# schematic.net
KiCad netlist of a schematic drawn in Altium Designer
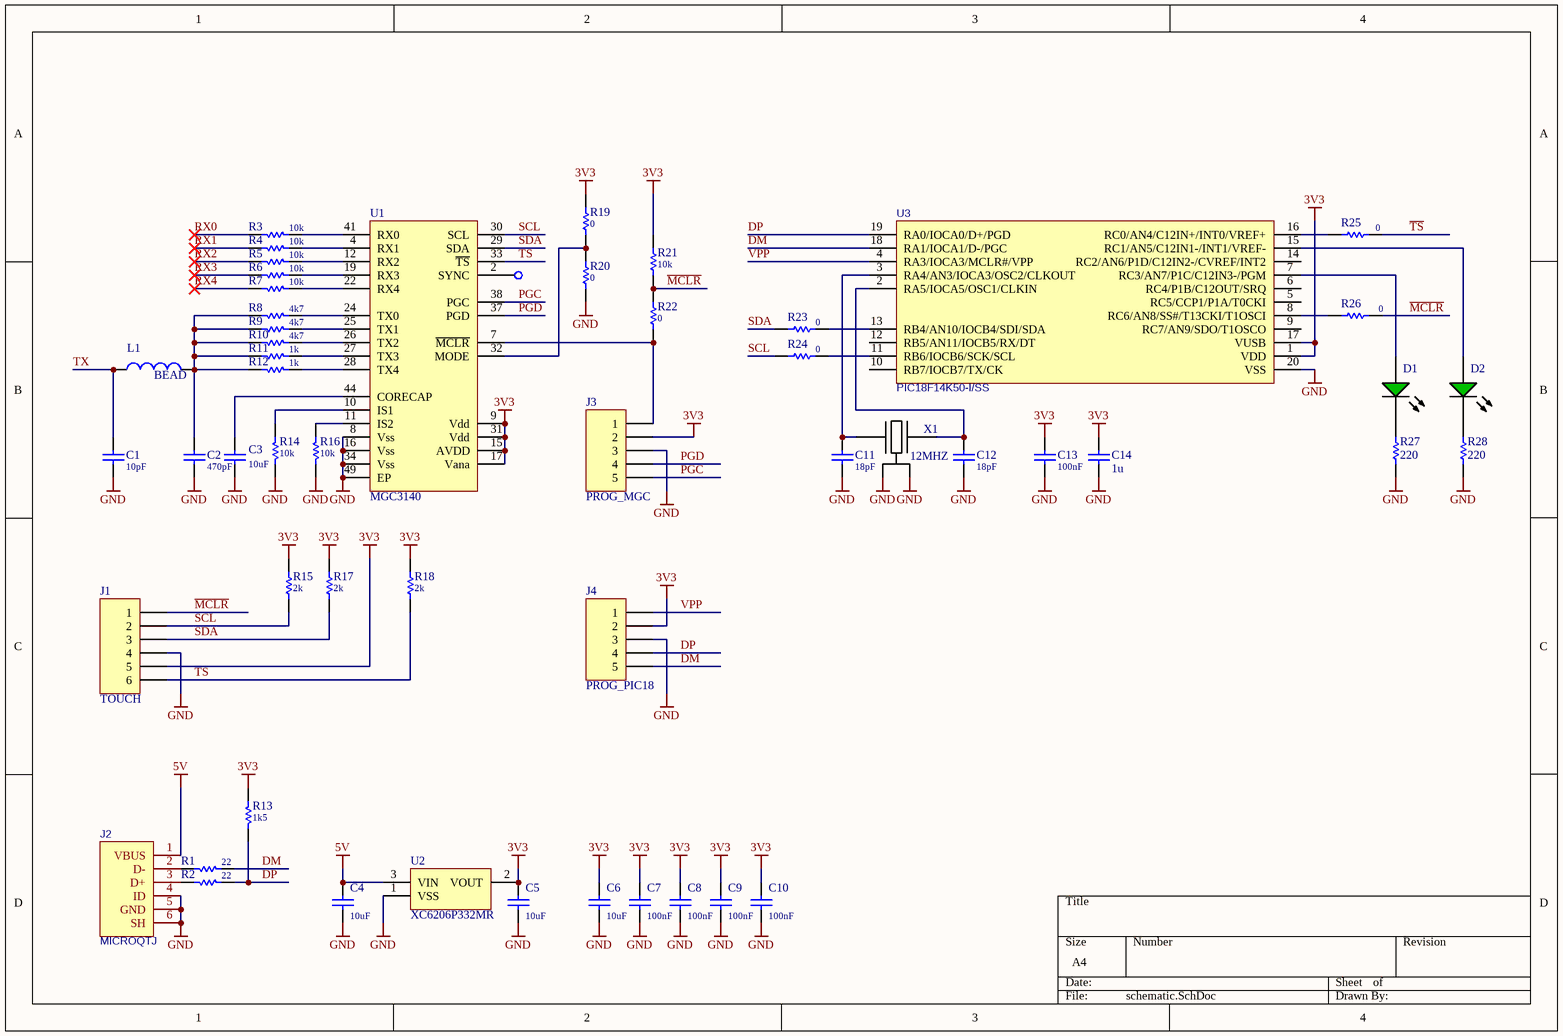
[diagram p0: schematic.SchDoc]

(export (version "E")
  (design (tool "Eeschema 10.0.6"))
  (components
    (comp (ref "C1")
      (value "10pF")
      (footprint "C0603")
      (libsource (lib "Miscellaneous Devices") (part "CAP"))
    )
    (comp (ref "C2")
      (value "470pF")
      (footprint "C0603")
      (libsource (lib "Miscellaneous Devices") (part "CAP"))
    )
    (comp (ref "C3")
      (value "10uF")
      (footprint "C0805")
      (libsource (lib "Miscellaneous Devices") (part "CAP"))
    )
    (comp (ref "C4")
      (value "10uF")
      (footprint "C1206")
      (libsource (lib "Miscellaneous Devices") (part "CAP"))
    )
    (comp (ref "C5")
      (value "10uF")
      (footprint "C1206")
      (libsource (lib "Miscellaneous Devices") (part "CAP"))
    )
    (comp (ref "C6")
      (value "10uF")
      (footprint "C0805")
      (libsource (lib "Miscellaneous Devices") (part "CAP"))
    )
    (comp (ref "C7")
      (value "100nF")
      (footprint "C0402")
      (libsource (lib "Miscellaneous Devices") (part "CAP"))
    )
    (comp (ref "C8")
      (value "100nF")
      (footprint "C0402")
      (libsource (lib "Miscellaneous Devices") (part "CAP"))
    )
    (comp (ref "C9")
      (value "100nF")
      (footprint "C0402")
      (libsource (lib "Miscellaneous Devices") (part "CAP"))
    )
    (comp (ref "C10")
      (value "100nF")
      (footprint "C0402")
      (libsource (lib "Miscellaneous Devices") (part "CAP"))
    )
    (comp (ref "C11")
      (value "18pF")
      (footprint "C0402")
      (description "18pF 50V 0402")
      (fields (field (name "LCSC PART NUMBER") "C33149"))
      (libsource (lib "Miscellaneous Devices") (part "CAP"))
    )
    (comp (ref "C12")
      (value "18pF")
      (footprint "C0402")
      (description "18pF 50V 0402")
      (fields (field (name "LCSC PART NUMBER") "C33149"))
      (libsource (lib "Miscellaneous Devices") (part "CAP"))
    )
    (comp (ref "C13")
      (value "100nF")
      (footprint "C0402")
      (libsource (lib "Miscellaneous Devices") (part "CAP"))
    )
    (comp (ref "C14") (value "1u") (footprint "C0603") (libsource (lib "Miscellaneous Devices") (part "Cap")))
    (comp (ref "D1")
      (value "GRN")
      (footprint "LED-0603-GRN")
      (description "LED 0603 GRN")
      (libsource (lib "Miscellaneous Devices") (part "LED-0603-GREEN"))
    )
    (comp (ref "D2")
      (value "GRN")
      (footprint "LED-0603-GRN")
      (description "LED 0603 GRN")
      (libsource (lib "Miscellaneous Devices") (part "LED-0603-GREEN"))
    )
    (comp (ref "DN1")
      (value "~")
      (footprint "PAD_CAST2_0.8MM")
      (libsource (lib "Schlib1") (part "dummy net"))
    )
    (comp (ref "J1") (value "TOUCH") (footprint "HDR-1X6_2.54") (libsource (lib "Schlib1") (part "Header 3")))
    (comp (ref "J2")
      (value "MICROQTJ")
      (footprint "CONN-USB-MICRO_#1")
      (libsource (lib "Schlib2") (part "MICROQTJ"))
    )
    (comp (ref "J3")
      (value "PROG_MGC")
      (footprint "HDR-1X5_2.54")
      (libsource (lib "Schlib1") (part "Header 5"))
    )
    (comp (ref "J4")
      (value "PROG_PIC18")
      (footprint "HDR-1X5_2.54")
      (libsource (lib "Schlib1") (part "Header 5"))
    )
    (comp (ref "L1")
      (value "BEAD")
      (footprint "L0603")
      (description "380mΩ ±25% 600Ω@100MHz 0603 Ferrite Beads")
      (fields (field (name "LCSC PART NUMBER") "C19330"))
      (libsource (lib "Miscellaneous Devices") (part "BLM18AG601SN1D"))
    )
    (comp (ref "R1") (value "22") (footprint "R0603") (libsource (lib "Miscellaneous Devices") (part "RES")))
    (comp (ref "R2") (value "22") (footprint "R0603") (libsource (lib "Miscellaneous Devices") (part "RES")))
    (comp (ref "R3")
      (value "10k")
      (footprint "R0603")
      (description "10k 0603")
      (libsource (lib "Miscellaneous Devices") (part "RES"))
    )
    (comp (ref "R4")
      (value "10k")
      (footprint "R0603")
      (description "10k 0603")
      (libsource (lib "Miscellaneous Devices") (part "RES"))
    )
    (comp (ref "R5")
      (value "10k")
      (footprint "R0603")
      (description "10k 0603")
      (libsource (lib "Miscellaneous Devices") (part "RES"))
    )
    (comp (ref "R6")
      (value "10k")
      (footprint "R0603")
      (description "10k 0603")
      (libsource (lib "Miscellaneous Devices") (part "RES"))
    )
    (comp (ref "R7")
      (value "10k")
      (footprint "R0603")
      (description "10k 0603")
      (libsource (lib "Miscellaneous Devices") (part "RES"))
    )
    (comp (ref "R8")
      (value "4k7")
      (footprint "R0603")
      (description "4k7 0603")
      (libsource (lib "Miscellaneous Devices") (part "RES"))
    )
    (comp (ref "R9")
      (value "4k7")
      (footprint "R0603")
      (description "4k7 0603")
      (libsource (lib "Miscellaneous Devices") (part "RES"))
    )
    (comp (ref "R10")
      (value "4k7")
      (footprint "R0603")
      (description "4k7 0603")
      (libsource (lib "Miscellaneous Devices") (part "RES"))
    )
    (comp (ref "R11")
      (value "1k")
      (footprint "R0603")
      (description "1k 0603")
      (libsource (lib "Miscellaneous Devices") (part "RES"))
    )
    (comp (ref "R12")
      (value "1k")
      (footprint "R0603")
      (description "1k 0603")
      (libsource (lib "Miscellaneous Devices") (part "RES"))
    )
    (comp (ref "R13")
      (value "1k5")
      (footprint "R0603")
      (description "1k5 0603")
      (libsource (lib "Miscellaneous Devices") (part "RES"))
    )
    (comp (ref "R14")
      (value "10k")
      (footprint "R0402")
      (libsource (lib "Miscellaneous Devices") (part "RES"))
    )
    (comp (ref "R15") (value "2k") (footprint "R0402") (libsource (lib "Miscellaneous Devices") (part "RES")))
    (comp (ref "R16")
      (value "10k")
      (footprint "R0402")
      (libsource (lib "Miscellaneous Devices") (part "RES"))
    )
    (comp (ref "R17") (value "2k") (footprint "R0402") (libsource (lib "Miscellaneous Devices") (part "RES")))
    (comp (ref "R18") (value "2k") (footprint "R0603") (libsource (lib "Miscellaneous Devices") (part "RES")))
    (comp (ref "R19")
      (value "0")
      (footprint "JMP0402_2")
      (libsource (lib "Miscellaneous Devices") (part "RES"))
    )
    (comp (ref "R20")
      (value "0")
      (footprint "JMP0402_2")
      (libsource (lib "Miscellaneous Devices") (part "RES"))
    )
    (comp (ref "R21")
      (value "10k")
      (footprint "R0603")
      (libsource (lib "Miscellaneous Devices") (part "RES"))
    )
    (comp (ref "R22")
      (value "0")
      (footprint "JMP0402_2")
      (libsource (lib "Miscellaneous Devices") (part "RES"))
    )
    (comp (ref "R23")
      (value "0")
      (footprint "JMP0402_2")
      (libsource (lib "Miscellaneous Devices") (part "RES"))
    )
    (comp (ref "R24")
      (value "0")
      (footprint "JMP0402_2")
      (libsource (lib "Miscellaneous Devices") (part "RES"))
    )
    (comp (ref "R25")
      (value "0")
      (footprint "JMP0402_2")
      (libsource (lib "Miscellaneous Devices") (part "RES"))
    )
    (comp (ref "R26")
      (value "0")
      (footprint "JMP0402_2")
      (libsource (lib "Miscellaneous Devices") (part "RES"))
    )
    (comp (ref "R27")
      (value "220")
      (footprint "R0603")
      (libsource (lib "Miscellaneous Devices") (part "Res1"))
    )
    (comp (ref "R28")
      (value "220")
      (footprint "R0603")
      (libsource (lib "Miscellaneous Devices") (part "Res1"))
    )
    (comp (ref "U1")
      (value "MGC3140")
      (footprint "QFN48_PT04_6X6")
      (libsource (lib "Schlib2") (part "Component_1_1"))
    )
    (comp (ref "U2")
      (value "XC6206P332MR")
      (footprint "SOT-23")
      (libsource (lib "Schlib1") (part "Component_4_1"))
    )
    (comp (ref "U3")
      (value "PIC18F14K50-I/SS")
      (footprint "SSOP-20")
      (fields (field (name "LCSC PART NUMBER") "C12460"))
      (libsource (lib "Schlib1") (part "PIC18F14K50-I/SS"))
    )
    (comp (ref "X1")
      (value "12MHZ")
      (footprint "CRYSTAL_3.2x2.5mm")
      (description "CRYSTAL 12MHZ 10PF SMD")
      (fields (field (name "LCSC PART NUMBER") "C70565"))
      (libsource (lib "Miscellaneous Devices") (part "CRYSTAL 12MHZ 3.20mm x 2.50mm"))
    )
  )
  (nets
    (net (code "1") (name "/DM") (class "Default")
      (node (ref "J4") (pin "5") (pinfunction "5_5") (pintype "passive"))
      (node (ref "R1") (pin "2") (pinfunction "2_2") (pintype "passive"))
      (node (ref "U3") (pin "18") (pinfunction "RA1/IOCA1/D-/PGC_18") (pintype "passive"))
    )
    (net (code "2") (name "/DP") (class "Default")
      (node (ref "J4") (pin "4") (pinfunction "4_4") (pintype "passive"))
      (node (ref "R13") (pin "1") (pinfunction "1_1") (pintype "passive"))
      (node (ref "R2") (pin "2") (pinfunction "2_2") (pintype "passive"))
      (node (ref "U3") (pin "19") (pinfunction "RA0/IOCA0/D+/PGD_19") (pintype "passive"))
    )
    (net (code "3") (name "/PGC") (class "Default")
      (node (ref "J3") (pin "5") (pinfunction "5_5") (pintype "passive"))
      (node (ref "U1") (pin "38") (pinfunction "PGC_38") (pintype "passive"))
    )
    (net (code "4") (name "/PGD") (class "Default")
      (node (ref "J3") (pin "4") (pinfunction "4_4") (pintype "passive"))
      (node (ref "U1") (pin "37") (pinfunction "PGD_37") (pintype "passive"))
    )
    (net (code "5") (name "/RX0") (class "Default")
      (node (ref "R3") (pin "1") (pinfunction "1_1") (pintype "passive+no_connect"))
    )
    (net (code "6") (name "/RX1") (class "Default")
      (node (ref "R4") (pin "1") (pinfunction "1_1") (pintype "passive+no_connect"))
    )
    (net (code "7") (name "/RX2") (class "Default")
      (node (ref "R5") (pin "1") (pinfunction "1_1") (pintype "passive+no_connect"))
    )
    (net (code "8") (name "/RX3") (class "Default")
      (node (ref "R6") (pin "1") (pinfunction "1_1") (pintype "passive+no_connect"))
    )
    (net (code "9") (name "/RX4") (class "Default")
      (node (ref "R7") (pin "1") (pinfunction "1_1") (pintype "passive+no_connect"))
    )
    (net (code "10") (name "/SCL") (class "Default")
      (node (ref "J1") (pin "2") (pinfunction "2_2") (pintype "passive"))
      (node (ref "R15") (pin "1") (pinfunction "1_1") (pintype "passive"))
      (node (ref "R24") (pin "2") (pinfunction "2_2") (pintype "passive"))
      (node (ref "U1") (pin "30") (pinfunction "SCL_30") (pintype "passive"))
    )
    (net (code "11") (name "/SDA") (class "Default")
      (node (ref "J1") (pin "3") (pinfunction "3_3") (pintype "passive"))
      (node (ref "R17") (pin "1") (pinfunction "1_1") (pintype "passive"))
      (node (ref "R23") (pin "2") (pinfunction "2_2") (pintype "passive"))
      (node (ref "U1") (pin "29") (pinfunction "SDA_29") (pintype "passive"))
    )
    (net (code "12") (name "/TX") (class "Default")
      (node (ref "C1") (pin "2") (pinfunction "2_2") (pintype "passive"))
      (node (ref "L1") (pin "2") (pinfunction "2_2") (pintype "passive"))
    )
    (net (code "13") (name "/VPP") (class "Default")
      (node (ref "J4") (pin "1") (pinfunction "1_1") (pintype "passive"))
      (node (ref "U3") (pin "4") (pinfunction "RA3/IOCA3/MCLR#/VPP_4") (pintype "passive"))
    )
    (net (code "14") (name "/~{MCLR}") (class "Default")
      (node (ref "J1") (pin "1") (pinfunction "1_1") (pintype "passive"))
      (node (ref "R21") (pin "1") (pinfunction "1_1") (pintype "passive"))
      (node (ref "R22") (pin "1") (pinfunction "1_1") (pintype "passive"))
      (node (ref "R26") (pin "1") (pinfunction "1_1") (pintype "passive"))
    )
    (net (code "15") (name "/~{TS}") (class "Default")
      (node (ref "J1") (pin "6") (pinfunction "6_6") (pintype "passive"))
      (node (ref "R18") (pin "1") (pinfunction "1_1") (pintype "passive"))
      (node (ref "R25") (pin "1") (pinfunction "1_1") (pintype "passive"))
      (node (ref "U1") (pin "33") (pinfunction "~{TS}_33") (pintype "passive"))
    )
    (net (code "16") (name "3V3") (class "Default")
      (node (ref "C10") (pin "2") (pinfunction "2_2") (pintype "passive"))
      (node (ref "C13") (pin "2") (pinfunction "2_2") (pintype "passive"))
      (node (ref "C14") (pin "2") (pinfunction "2_2") (pintype "passive"))
      (node (ref "C5") (pin "2") (pinfunction "2_2") (pintype "passive"))
      (node (ref "C6") (pin "2") (pinfunction "2_2") (pintype "passive"))
      (node (ref "C7") (pin "2") (pinfunction "2_2") (pintype "passive"))
      (node (ref "C8") (pin "2") (pinfunction "2_2") (pintype "passive"))
      (node (ref "C9") (pin "2") (pinfunction "2_2") (pintype "passive"))
      (node (ref "J1") (pin "5") (pinfunction "5_5") (pintype "passive"))
      (node (ref "J3") (pin "2") (pinfunction "2_2") (pintype "passive"))
      (node (ref "J4") (pin "2") (pinfunction "2_2") (pintype "passive"))
      (node (ref "R13") (pin "2") (pinfunction "2_2") (pintype "passive"))
      (node (ref "R15") (pin "2") (pinfunction "2_2") (pintype "passive"))
      (node (ref "R17") (pin "2") (pinfunction "2_2") (pintype "passive"))
      (node (ref "R18") (pin "2") (pinfunction "2_2") (pintype "passive"))
      (node (ref "R19") (pin "1") (pinfunction "1_1") (pintype "passive"))
      (node (ref "R21") (pin "2") (pinfunction "2_2") (pintype "passive"))
      (node (ref "U1") (pin "15") (pinfunction "AVDD_15") (pintype "passive"))
      (node (ref "U1") (pin "17") (pinfunction "Vana_17") (pintype "passive"))
      (node (ref "U1") (pin "31") (pinfunction "Vdd_31") (pintype "passive"))
      (node (ref "U1") (pin "9") (pinfunction "Vdd_9") (pintype "passive"))
      (node (ref "U2") (pin "2") (pinfunction "VOUT_2") (pintype "passive"))
      (node (ref "U3") (pin "1") (pinfunction "VDD_1") (pintype "passive"))
      (node (ref "U3") (pin "17") (pinfunction "VUSB_17") (pintype "passive"))
    )
    (net (code "17") (name "5V") (class "Default")
      (node (ref "C4") (pin "2") (pinfunction "2_2") (pintype "passive"))
      (node (ref "J2") (pin "1") (pinfunction "VBUS_1") (pintype "passive"))
      (node (ref "U2") (pin "3") (pinfunction "VIN_3") (pintype "passive"))
    )
    (net (code "18") (name "GND") (class "Default")
      (node (ref "C1") (pin "1") (pinfunction "1_1") (pintype "passive"))
      (node (ref "C10") (pin "1") (pinfunction "1_1") (pintype "passive"))
      (node (ref "C11") (pin "1") (pinfunction "1_1") (pintype "passive"))
      (node (ref "C12") (pin "1") (pinfunction "1_1") (pintype "passive"))
      (node (ref "C13") (pin "1") (pinfunction "1_1") (pintype "passive"))
      (node (ref "C14") (pin "1") (pinfunction "1_1") (pintype "passive"))
      (node (ref "C2") (pin "1") (pinfunction "1_1") (pintype "passive"))
      (node (ref "C3") (pin "1") (pinfunction "1_1") (pintype "passive"))
      (node (ref "C4") (pin "1") (pinfunction "1_1") (pintype "passive"))
      (node (ref "C5") (pin "1") (pinfunction "1_1") (pintype "passive"))
      (node (ref "C6") (pin "1") (pinfunction "1_1") (pintype "passive"))
      (node (ref "C7") (pin "1") (pinfunction "1_1") (pintype "passive"))
      (node (ref "C8") (pin "1") (pinfunction "1_1") (pintype "passive"))
      (node (ref "C9") (pin "1") (pinfunction "1_1") (pintype "passive"))
      (node (ref "J1") (pin "4") (pinfunction "4_4") (pintype "passive"))
      (node (ref "J2") (pin "4") (pinfunction "ID_4") (pintype "passive"))
      (node (ref "J2") (pin "5") (pinfunction "GND_5") (pintype "passive"))
      (node (ref "J2") (pin "6") (pinfunction "SH_6") (pintype "passive"))
      (node (ref "J3") (pin "3") (pinfunction "3_3") (pintype "passive"))
      (node (ref "J4") (pin "3") (pinfunction "3_3") (pintype "passive"))
      (node (ref "R14") (pin "1") (pinfunction "1_1") (pintype "passive"))
      (node (ref "R16") (pin "1") (pinfunction "1_1") (pintype "passive"))
      (node (ref "R20") (pin "2") (pinfunction "2_2") (pintype "passive"))
      (node (ref "R27") (pin "1") (pinfunction "1_1") (pintype "passive"))
      (node (ref "R28") (pin "1") (pinfunction "1_1") (pintype "passive"))
      (node (ref "U1") (pin "16") (pinfunction "Vss_16") (pintype "passive"))
      (node (ref "U1") (pin "34") (pinfunction "Vss_34") (pintype "passive"))
      (node (ref "U1") (pin "49") (pinfunction "EP_49") (pintype "passive"))
      (node (ref "U1") (pin "8") (pinfunction "Vss_8") (pintype "passive"))
      (node (ref "U2") (pin "1") (pinfunction "VSS_1") (pintype "passive"))
      (node (ref "U3") (pin "20") (pinfunction "VSS_20") (pintype "passive"))
      (node (ref "X1") (pin "2") (pinfunction "GND_2") (pintype "passive"))
      (node (ref "X1") (pin "4") (pinfunction "GND_4") (pintype "passive"))
    )
    (net (code "19") (name "Net-(C2-Pad2)") (class "Default")
      (node (ref "C2") (pin "2") (pinfunction "2_2") (pintype "passive"))
      (node (ref "L1") (pin "1") (pinfunction "1_1") (pintype "passive"))
      (node (ref "R10") (pin "1") (pinfunction "1_1") (pintype "passive"))
      (node (ref "R11") (pin "1") (pinfunction "1_1") (pintype "passive"))
      (node (ref "R12") (pin "1") (pinfunction "1_1") (pintype "passive"))
      (node (ref "R8") (pin "1") (pinfunction "1_1") (pintype "passive"))
      (node (ref "R9") (pin "1") (pinfunction "1_1") (pintype "passive"))
    )
    (net (code "20") (name "Net-(D1-A)") (class "Default")
      (node (ref "D1") (pin "1") (pinfunction "A_1") (pintype "passive"))
      (node (ref "U3") (pin "7") (pinfunction "RC3/AN7/P1C/C12IN3-/PGM_7") (pintype "passive"))
    )
    (net (code "21") (name "Net-(D1-K)") (class "Default")
      (node (ref "D1") (pin "2") (pinfunction "K_2") (pintype "passive"))
      (node (ref "R27") (pin "2") (pinfunction "2_2") (pintype "passive"))
    )
    (net (code "22") (name "Net-(D2-A)") (class "Default")
      (node (ref "D2") (pin "1") (pinfunction "A_1") (pintype "passive"))
      (node (ref "U3") (pin "15") (pinfunction "RC1/AN5/C12IN1-/INT1/VREF-_15") (pintype "passive"))
    )
    (net (code "23") (name "Net-(D2-K)") (class "Default")
      (node (ref "D2") (pin "2") (pinfunction "K_2") (pintype "passive"))
      (node (ref "R28") (pin "2") (pinfunction "2_2") (pintype "passive"))
    )
    (net (code "24") (name "Net-(J2-D+)") (class "Default")
      (node (ref "J2") (pin "3") (pinfunction "D+_3") (pintype "passive"))
      (node (ref "R2") (pin "1") (pinfunction "1_1") (pintype "passive"))
    )
    (net (code "25") (name "Net-(J2-D-)") (class "Default")
      (node (ref "J2") (pin "2") (pinfunction "D-_2") (pintype "passive"))
      (node (ref "R1") (pin "1") (pinfunction "1_1") (pintype "passive"))
    )
    (net (code "26") (name "Net-(U1-CORECAP)") (class "Default")
      (node (ref "C3") (pin "2") (pinfunction "2_2") (pintype "passive"))
      (node (ref "U1") (pin "44") (pinfunction "CORECAP_44") (pintype "passive"))
    )
    (net (code "27") (name "Net-(U1-IS1)") (class "Default")
      (node (ref "R14") (pin "2") (pinfunction "2_2") (pintype "passive"))
      (node (ref "U1") (pin "10") (pinfunction "IS1_10") (pintype "passive"))
    )
    (net (code "28") (name "Net-(U1-IS2)") (class "Default")
      (node (ref "R16") (pin "2") (pinfunction "2_2") (pintype "passive"))
      (node (ref "U1") (pin "11") (pinfunction "IS2_11") (pintype "passive"))
    )
    (net (code "29") (name "Net-(U1-MODE)") (class "Default")
      (node (ref "R19") (pin "2") (pinfunction "2_2") (pintype "passive"))
      (node (ref "R20") (pin "1") (pinfunction "1_1") (pintype "passive"))
      (node (ref "U1") (pin "32") (pinfunction "MODE_32") (pintype "passive"))
    )
    (net (code "30") (name "Net-(U1-RX0)") (class "Default")
      (node (ref "R3") (pin "2") (pinfunction "2_2") (pintype "passive"))
      (node (ref "U1") (pin "41") (pinfunction "RX0_41") (pintype "passive"))
    )
    (net (code "31") (name "Net-(U1-RX1)") (class "Default")
      (node (ref "R4") (pin "2") (pinfunction "2_2") (pintype "passive"))
      (node (ref "U1") (pin "4") (pinfunction "RX1_4") (pintype "passive"))
    )
    (net (code "32") (name "Net-(U1-RX2)") (class "Default")
      (node (ref "R5") (pin "2") (pinfunction "2_2") (pintype "passive"))
      (node (ref "U1") (pin "12") (pinfunction "RX2_12") (pintype "passive"))
    )
    (net (code "33") (name "Net-(U1-RX3)") (class "Default")
      (node (ref "R6") (pin "2") (pinfunction "2_2") (pintype "passive"))
      (node (ref "U1") (pin "19") (pinfunction "RX3_19") (pintype "passive"))
    )
    (net (code "34") (name "Net-(U1-RX4)") (class "Default")
      (node (ref "R7") (pin "2") (pinfunction "2_2") (pintype "passive"))
      (node (ref "U1") (pin "22") (pinfunction "RX4_22") (pintype "passive"))
    )
    (net (code "35") (name "Net-(U1-SYNC)") (class "Default")
      (node (ref "DN1") (pin "1") (pinfunction "1_1") (pintype "passive"))
      (node (ref "U1") (pin "2") (pinfunction "SYNC_2") (pintype "passive"))
    )
    (net (code "36") (name "Net-(U1-TX0)") (class "Default")
      (node (ref "R8") (pin "2") (pinfunction "2_2") (pintype "passive"))
      (node (ref "U1") (pin "24") (pinfunction "TX0_24") (pintype "passive"))
    )
    (net (code "37") (name "Net-(U1-TX1)") (class "Default")
      (node (ref "R9") (pin "2") (pinfunction "2_2") (pintype "passive"))
      (node (ref "U1") (pin "25") (pinfunction "TX1_25") (pintype "passive"))
    )
    (net (code "38") (name "Net-(U1-TX2)") (class "Default")
      (node (ref "R10") (pin "2") (pinfunction "2_2") (pintype "passive"))
      (node (ref "U1") (pin "26") (pinfunction "TX2_26") (pintype "passive"))
    )
    (net (code "39") (name "Net-(U1-TX3)") (class "Default")
      (node (ref "R11") (pin "2") (pinfunction "2_2") (pintype "passive"))
      (node (ref "U1") (pin "27") (pinfunction "TX3_27") (pintype "passive"))
    )
    (net (code "40") (name "Net-(U1-TX4)") (class "Default")
      (node (ref "R12") (pin "2") (pinfunction "2_2") (pintype "passive"))
      (node (ref "U1") (pin "28") (pinfunction "TX4_28") (pintype "passive"))
    )
    (net (code "41") (name "Net-(U1-~{MCLR})") (class "Default")
      (node (ref "J3") (pin "1") (pinfunction "1_1") (pintype "passive"))
      (node (ref "R22") (pin "2") (pinfunction "2_2") (pintype "passive"))
      (node (ref "U1") (pin "7") (pinfunction "~{MCLR}_7") (pintype "passive"))
    )
    (net (code "42") (name "Net-(U3-RA4{slash}AN3{slash}IOCA3{slash}OSC2{slash}CLKOUT)") (class "Default")
      (node (ref "C11") (pin "2") (pinfunction "2_2") (pintype "passive"))
      (node (ref "U3") (pin "3") (pinfunction "RA4/AN3/IOCA3/OSC2/CLKOUT_3") (pintype "passive"))
      (node (ref "X1") (pin "1") (pinfunction "X1_1") (pintype "passive"))
    )
    (net (code "43") (name "Net-(U3-RA5{slash}IOCA5{slash}OSC1{slash}CLKIN)") (class "Default")
      (node (ref "C12") (pin "2") (pinfunction "2_2") (pintype "passive"))
      (node (ref "U3") (pin "2") (pinfunction "RA5/IOCA5/OSC1/CLKIN_2") (pintype "passive"))
      (node (ref "X1") (pin "3") (pinfunction "X2_3") (pintype "passive"))
    )
    (net (code "44") (name "Net-(U3-RB4{slash}AN10{slash}IOCB4{slash}SDI{slash}SDA)") (class "Default")
      (node (ref "R23") (pin "1") (pinfunction "1_1") (pintype "passive"))
      (node (ref "U3") (pin "13") (pinfunction "RB4/AN10/IOCB4/SDI/SDA_13") (pintype "passive"))
    )
    (net (code "45") (name "Net-(U3-RB6{slash}IOCB6{slash}SCK{slash}SCL)") (class "Default")
      (node (ref "R24") (pin "1") (pinfunction "1_1") (pintype "passive"))
      (node (ref "U3") (pin "11") (pinfunction "RB6/IOCB6/SCK/SCL_11") (pintype "passive"))
    )
    (net (code "46") (name "Net-(U3-RC0{slash}AN4{slash}C12IN+{slash}INT0{slash}VREF+)") (class "Default")
      (node (ref "R25") (pin "2") (pinfunction "2_2") (pintype "passive"))
      (node (ref "U3") (pin "16") (pinfunction "RC0/AN4/C12IN+/INT0/VREF+_16") (pintype "passive"))
    )
    (net (code "47") (name "Net-(U3-RC6{slash}AN8{slash}SS#{slash}T13CKI{slash}T1OSCI)") (class "Default")
      (node (ref "R26") (pin "2") (pinfunction "2_2") (pintype "passive"))
      (node (ref "U3") (pin "8") (pinfunction "RC6/AN8/SS#/T13CKI/T1OSCI_8") (pintype "passive"))
    )
    (net (code "48") (name "unconnected-(U3-RB5{slash}AN11{slash}IOCB5{slash}RX{slash}DT-Pad12)") (class "Default")
      (node (ref "U3") (pin "12") (pinfunction "RB5/AN11/IOCB5/RX/DT_12") (pintype "passive"))
    )
    (net (code "49") (name "unconnected-(U3-RB7{slash}IOCB7{slash}TX{slash}CK-Pad10)") (class "Default")
      (node (ref "U3") (pin "10") (pinfunction "RB7/IOCB7/TX/CK_10") (pintype "passive"))
    )
    (net (code "50") (name "unconnected-(U3-RC2{slash}AN6{slash}P1D{slash}C12IN2-{slash}CVREF{slash}INT2-Pad14)") (class "Default")
      (node (ref "U3") (pin "14") (pinfunction "RC2/AN6/P1D/C12IN2-/CVREF/INT2_14") (pintype "passive"))
    )
    (net (code "51") (name "unconnected-(U3-RC4{slash}P1B{slash}C12OUT{slash}SRQ-Pad6)") (class "Default")
      (node (ref "U3") (pin "6") (pinfunction "RC4/P1B/C12OUT/SRQ_6") (pintype "passive"))
    )
    (net (code "52") (name "unconnected-(U3-RC5{slash}CCP1{slash}P1A{slash}T0CKI-Pad5)") (class "Default")
      (node (ref "U3") (pin "5") (pinfunction "RC5/CCP1/P1A/T0CKI_5") (pintype "passive"))
    )
    (net (code "53") (name "unconnected-(U3-RC7{slash}AN9{slash}SDO{slash}T1OSCO-Pad9)") (class "Default")
      (node (ref "U3") (pin "9") (pinfunction "RC7/AN9/SDO/T1OSCO_9") (pintype "passive"))
    )
  )
)
